# captouch_reva.net
KiCad netlist of a schematic drawn in EAGLE
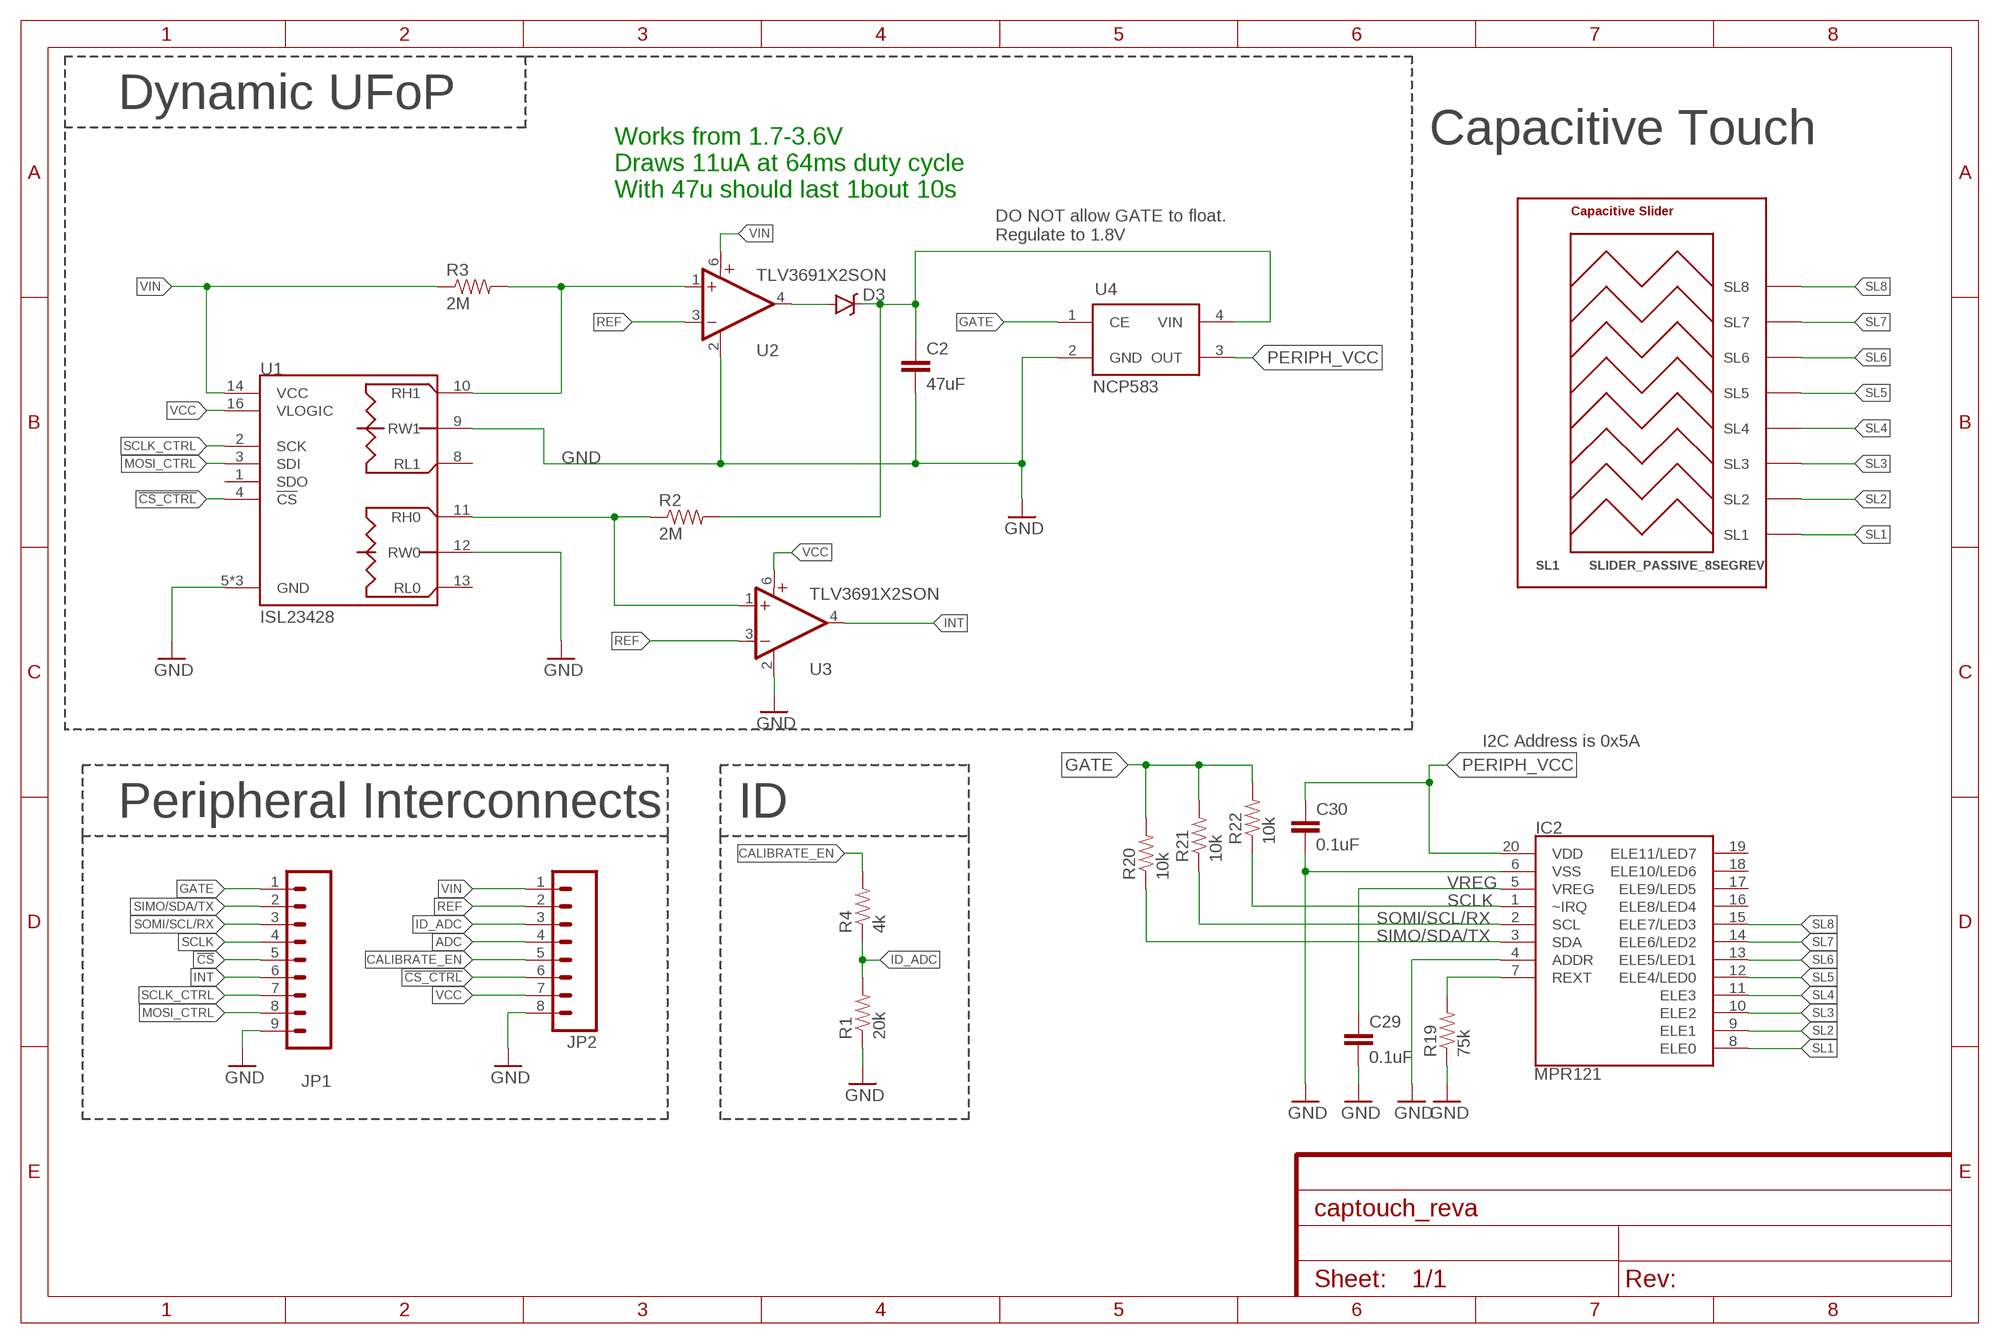
[diagram p0: schematic, sheet 1]

(export (version "E")
  (design (tool "Eeschema 10.0.6"))
  (components
    (comp (ref "C2")
      (value "47uF")
      (footprint "eagle-import:0805")
      (fields (field (name "MPN") "GRM21BR60J476ME15L"))
      (libsource (lib "eagle-import") (part "CAP0805"))
    )
    (comp (ref "C29")
      (value "0.1uF")
      (footprint "eagle-import:0402")
      (fields (field (name "MPN") "0402YD104KAT2A"))
      (libsource (lib "eagle-import") (part "C-EU"))
    )
    (comp (ref "C30")
      (value "0.1uF")
      (footprint "eagle-import:0402")
      (fields (field (name "MPN") "0402YD104KAT2A"))
      (libsource (lib "eagle-import") (part "C-EU"))
    )
    (comp (ref "D3")
      (value "RB751")
      (footprint "eagle-import:SOD-523")
      (fields (field (name "MPN") "BAS40-02V-V-G-08"))
      (libsource (lib "eagle-import") (part "DIODE-SCHOTTKY-RB751"))
    )
    (comp (ref "IC2")
      (value "MPR121")
      (footprint "eagle-import:QFN-20-0.4MM-V2")
      (fields (field (name "MPN") "MPR121QR2 "))
      (libsource (lib "eagle-import") (part "MPR121V2"))
    )
    (comp (ref "JP1")
      (value "M091.27MM")
      (footprint "eagle-import:1X09-1.27MM")
      (fields (field (name "MPN") "GRPB091VWVN-RC "))
      (libsource (lib "eagle-import") (part "M091.27MM"))
    )
    (comp (ref "JP2")
      (value "M081.27MM")
      (footprint "eagle-import:1X08-1.27MM")
      (fields (field (name "MPN") "GRPB081VWVN-RC "))
      (libsource (lib "eagle-import") (part "M081.27MM"))
    )
    (comp (ref "R1")
      (value "20k")
      (footprint "eagle-import:0402")
      (fields (field (name "MPN") "ERJ-2RKF2002X"))
      (libsource (lib "eagle-import") (part "R-EU"))
    )
    (comp (ref "R2")
      (value "2M")
      (footprint "eagle-import:0402")
      (fields (field (name "MPN") "RC1005F205CS"))
      (libsource (lib "eagle-import") (part "R-EU"))
    )
    (comp (ref "R3")
      (value "2M")
      (footprint "eagle-import:0402")
      (fields (field (name "MPN") "RC1005F205CS"))
      (libsource (lib "eagle-import") (part "R-EU"))
    )
    (comp (ref "R4")
      (value "4k")
      (footprint "eagle-import:0402")
      (fields (field (name "MPN") "RC0402FR-074K02L"))
      (libsource (lib "eagle-import") (part "R-EU"))
    )
    (comp (ref "R19")
      (value "75k")
      (footprint "eagle-import:0402")
      (fields (field (name "MPN") "RC0402FR-0775KL"))
      (libsource (lib "eagle-import") (part "R-EU"))
    )
    (comp (ref "R20")
      (value "10k")
      (footprint "eagle-import:0402")
      (fields (field (name "MPN") "ERJ-2RKF1002X"))
      (libsource (lib "eagle-import") (part "R-EU"))
    )
    (comp (ref "R21")
      (value "10k")
      (footprint "eagle-import:0402")
      (fields (field (name "MPN") "ERJ-2RKF1002X"))
      (libsource (lib "eagle-import") (part "R-EU"))
    )
    (comp (ref "R22")
      (value "10k")
      (footprint "eagle-import:0402")
      (fields (field (name "MPN") "ERJ-2RKF1002X"))
      (libsource (lib "eagle-import") (part "R-EU"))
    )
    (comp (ref "SL1")
      (value "SLIDER_PASSIVE_8SEGREV")
      (footprint "eagle-import:SLIDER_PASSIVE_8SEG_12MM_REV")
      (libsource (lib "eagle-import") (part "SLIDER_PASSIVE_8SEGREV"))
    )
    (comp (ref "U1")
      (value "ISL23428")
      (footprint "eagle-import:UTQFN-16")
      (fields (field (name "MPN") "ISL23428TFRUZ-T7A"))
      (libsource (lib "eagle-import") (part "ISL23428"))
    )
    (comp (ref "U2")
      (value "TLV3691X2SON")
      (footprint "eagle-import:X2SON")
      (fields (field (name "MPN") "TLV3691IDPFR"))
      (libsource (lib "eagle-import") (part "TLV3691X2SON"))
    )
    (comp (ref "U3")
      (value "TLV3691X2SON")
      (footprint "eagle-import:X2SON")
      (fields (field (name "MPN") "TLV3691IDPFR"))
      (libsource (lib "eagle-import") (part "TLV3691X2SON"))
    )
    (comp (ref "U4")
      (value "NCP583")
      (footprint "eagle-import:SC82-AB_1PRIMARY")
      (fields (field (name "MPN") "NCP583SQ18T1G"))
      (libsource (lib "eagle-import") (part "NCP583"))
    )
  )
  (nets
    (net (code "1") (name "/VREG") (class "Default")
      (node (ref "C29") (pin "1") (pinfunction "1_1") (pintype "passive"))
      (node (ref "IC2") (pin "5") (pinfunction "VREG_5") (pintype "bidirectional"))
    )
    (net (code "2") (name "/~{CS_CTRL}") (class "Default")
      (node (ref "JP2") (pin "6") (pinfunction "6_6") (pintype "passive"))
      (node (ref "U1") (pin "4") (pinfunction "~{CS}_4") (pintype "bidirectional"))
    )
    (net (code "3") (name "/~{CS}") (class "Default")
      (node (ref "JP1") (pin "5") (pinfunction "5_5") (pintype "passive"))
    )
    (net (code "4") (name "ADC") (class "Default")
      (node (ref "JP2") (pin "4") (pinfunction "4_4") (pintype "passive"))
    )
    (net (code "5") (name "CALIBRATE_EN") (class "Default")
      (node (ref "JP2") (pin "5") (pinfunction "5_5") (pintype "passive"))
      (node (ref "R4") (pin "2") (pinfunction "2_2") (pintype "passive"))
    )
    (net (code "6") (name "GATE") (class "Default")
      (node (ref "JP1") (pin "1") (pinfunction "1_1") (pintype "passive"))
      (node (ref "R20") (pin "2") (pinfunction "2_2") (pintype "passive"))
      (node (ref "R21") (pin "2") (pinfunction "2_2") (pintype "passive"))
      (node (ref "R22") (pin "2") (pinfunction "2_2") (pintype "passive"))
      (node (ref "U4") (pin "1") (pinfunction "CE_1") (pintype "bidirectional"))
    )
    (net (code "7") (name "GND") (class "Default")
      (node (ref "C2") (pin "2") (pinfunction "2_2") (pintype "passive"))
      (node (ref "C29") (pin "2") (pinfunction "2_2") (pintype "passive"))
      (node (ref "C30") (pin "2") (pinfunction "2_2") (pintype "passive"))
      (node (ref "IC2") (pin "4") (pinfunction "ADDR_4") (pintype "bidirectional"))
      (node (ref "IC2") (pin "6") (pinfunction "VSS_6") (pintype "bidirectional"))
      (node (ref "JP1") (pin "9") (pinfunction "9_9") (pintype "passive"))
      (node (ref "JP2") (pin "8") (pinfunction "8_8") (pintype "passive"))
      (node (ref "R1") (pin "1") (pinfunction "1_1") (pintype "passive"))
      (node (ref "R19") (pin "1") (pinfunction "1_1") (pintype "passive"))
      (node (ref "U1") (pin "12") (pinfunction "RW0_12") (pintype "bidirectional"))
      (node (ref "U1") (pin "15") (pinfunction "GND_15") (pintype "bidirectional"))
      (node (ref "U1") (pin "5") (pinfunction "GND_5") (pintype "bidirectional"))
      (node (ref "U1") (pin "6") (pinfunction "GND_6") (pintype "bidirectional"))
      (node (ref "U1") (pin "9") (pinfunction "RW1_9") (pintype "bidirectional"))
      (node (ref "U2") (pin "2") (pinfunction "GND_2") (pintype "power_in"))
      (node (ref "U3") (pin "2") (pinfunction "GND_2") (pintype "power_in"))
      (node (ref "U4") (pin "2") (pinfunction "GND_2") (pintype "bidirectional"))
    )
    (net (code "8") (name "ID_ADC") (class "Default")
      (node (ref "JP2") (pin "3") (pinfunction "3_3") (pintype "passive"))
      (node (ref "R1") (pin "2") (pinfunction "2_2") (pintype "passive"))
      (node (ref "R4") (pin "1") (pinfunction "1_1") (pintype "passive"))
    )
    (net (code "9") (name "INT") (class "Default")
      (node (ref "JP1") (pin "6") (pinfunction "6_6") (pintype "passive"))
      (node (ref "U3") (pin "4") (pinfunction "OUT_4") (pintype "output"))
    )
    (net (code "10") (name "MOSI_CTRL") (class "Default")
      (node (ref "JP1") (pin "8") (pinfunction "8_8") (pintype "passive"))
      (node (ref "U1") (pin "3") (pinfunction "SDI_3") (pintype "bidirectional"))
    )
    (net (code "11") (name "Net-(IC2-REXT)") (class "Default")
      (node (ref "IC2") (pin "7") (pinfunction "REXT_7") (pintype "bidirectional"))
      (node (ref "R19") (pin "2") (pinfunction "2_2") (pintype "passive"))
    )
    (net (code "12") (name "Net-(U1-RH0)") (class "Default")
      (node (ref "R2") (pin "1") (pinfunction "1_1") (pintype "passive"))
      (node (ref "U1") (pin "11") (pinfunction "RH0_11") (pintype "bidirectional"))
      (node (ref "U3") (pin "1") (pinfunction "+IN_1") (pintype "input"))
    )
    (net (code "13") (name "Net-(U1-RH1)") (class "Default")
      (node (ref "R3") (pin "2") (pinfunction "2_2") (pintype "passive"))
      (node (ref "U1") (pin "10") (pinfunction "RH1_10") (pintype "bidirectional"))
      (node (ref "U2") (pin "1") (pinfunction "+IN_1") (pintype "input"))
    )
    (net (code "14") (name "Net-(U2-OUT)") (class "Default")
      (node (ref "D3") (pin "A") (pinfunction "A_A") (pintype "passive"))
      (node (ref "U2") (pin "4") (pinfunction "OUT_4") (pintype "output"))
    )
    (net (code "15") (name "Net-(U4-VIN)") (class "Default")
      (node (ref "C2") (pin "1") (pinfunction "1_1") (pintype "passive"))
      (node (ref "D3") (pin "C") (pinfunction "C_C") (pintype "passive"))
      (node (ref "R2") (pin "2") (pinfunction "2_2") (pintype "passive"))
      (node (ref "U4") (pin "4") (pinfunction "VIN_4") (pintype "bidirectional"))
    )
    (net (code "16") (name "PERIPH_VCC") (class "Default")
      (node (ref "C30") (pin "1") (pinfunction "1_1") (pintype "passive"))
      (node (ref "IC2") (pin "20") (pinfunction "VDD_20") (pintype "bidirectional"))
      (node (ref "U4") (pin "3") (pinfunction "OUT_3") (pintype "bidirectional"))
    )
    (net (code "17") (name "REF") (class "Default")
      (node (ref "JP2") (pin "2") (pinfunction "2_2") (pintype "passive"))
      (node (ref "U2") (pin "3") (pinfunction "-IN_3") (pintype "input"))
      (node (ref "U3") (pin "3") (pinfunction "-IN_3") (pintype "input"))
    )
    (net (code "18") (name "SCLK") (class "Default")
      (node (ref "IC2") (pin "1") (pinfunction "~{IRQ}_1") (pintype "bidirectional"))
      (node (ref "JP1") (pin "4") (pinfunction "4_4") (pintype "passive"))
      (node (ref "R22") (pin "1") (pinfunction "1_1") (pintype "passive"))
    )
    (net (code "19") (name "SCLK_CTRL") (class "Default")
      (node (ref "JP1") (pin "7") (pinfunction "7_7") (pintype "passive"))
      (node (ref "U1") (pin "2") (pinfunction "SCK_2") (pintype "bidirectional"))
    )
    (net (code "20") (name "SIMO{slash}SDA{slash}TX") (class "Default")
      (node (ref "IC2") (pin "3") (pinfunction "SDA_3") (pintype "bidirectional"))
      (node (ref "JP1") (pin "2") (pinfunction "2_2") (pintype "passive"))
      (node (ref "R20") (pin "1") (pinfunction "1_1") (pintype "passive"))
    )
    (net (code "21") (name "SL1") (class "Default")
      (node (ref "IC2") (pin "8") (pinfunction "ELE0_8") (pintype "bidirectional"))
      (node (ref "SL1") (pin "SL1") (pinfunction "SL1_SL1") (pintype "passive"))
    )
    (net (code "22") (name "SL2") (class "Default")
      (node (ref "IC2") (pin "9") (pinfunction "ELE1_9") (pintype "bidirectional"))
      (node (ref "SL1") (pin "SL2") (pinfunction "SL2_SL2") (pintype "passive"))
    )
    (net (code "23") (name "SL3") (class "Default")
      (node (ref "IC2") (pin "10") (pinfunction "ELE2_10") (pintype "bidirectional"))
      (node (ref "SL1") (pin "SL3") (pinfunction "SL3_SL3") (pintype "passive"))
    )
    (net (code "24") (name "SL4") (class "Default")
      (node (ref "IC2") (pin "11") (pinfunction "ELE3_11") (pintype "bidirectional"))
      (node (ref "SL1") (pin "SL4") (pinfunction "SL4_SL4") (pintype "passive"))
    )
    (net (code "25") (name "SL5") (class "Default")
      (node (ref "IC2") (pin "12") (pinfunction "ELE4/LED0_12") (pintype "bidirectional"))
      (node (ref "SL1") (pin "SL5") (pinfunction "SL5_SL5") (pintype "passive"))
    )
    (net (code "26") (name "SL6") (class "Default")
      (node (ref "IC2") (pin "13") (pinfunction "ELE5/LED1_13") (pintype "bidirectional"))
      (node (ref "SL1") (pin "SL6") (pinfunction "SL6_SL6") (pintype "passive"))
    )
    (net (code "27") (name "SL7") (class "Default")
      (node (ref "IC2") (pin "14") (pinfunction "ELE6/LED2_14") (pintype "bidirectional"))
      (node (ref "SL1") (pin "SL7") (pinfunction "SL7_SL7") (pintype "passive"))
    )
    (net (code "28") (name "SL8") (class "Default")
      (node (ref "IC2") (pin "15") (pinfunction "ELE7/LED3_15") (pintype "bidirectional"))
      (node (ref "SL1") (pin "SL8") (pinfunction "SL8_SL8") (pintype "passive"))
    )
    (net (code "29") (name "SOMI{slash}SCL{slash}RX") (class "Default")
      (node (ref "IC2") (pin "2") (pinfunction "SCL_2") (pintype "bidirectional"))
      (node (ref "JP1") (pin "3") (pinfunction "3_3") (pintype "passive"))
      (node (ref "R21") (pin "1") (pinfunction "1_1") (pintype "passive"))
    )
    (net (code "30") (name "VCC") (class "Default")
      (node (ref "JP2") (pin "7") (pinfunction "7_7") (pintype "passive"))
      (node (ref "U1") (pin "16") (pinfunction "VLOGIC_16") (pintype "bidirectional"))
      (node (ref "U3") (pin "6") (pinfunction "V+_6") (pintype "power_in"))
    )
    (net (code "31") (name "VIN") (class "Default")
      (node (ref "JP2") (pin "1") (pinfunction "1_1") (pintype "passive"))
      (node (ref "R3") (pin "1") (pinfunction "1_1") (pintype "passive"))
      (node (ref "U1") (pin "14") (pinfunction "VCC_14") (pintype "bidirectional"))
      (node (ref "U2") (pin "6") (pinfunction "V+_6") (pintype "power_in"))
    )
    (net (code "32") (name "unconnected-(IC2-ELE8{slash}LED4-Pad16)") (class "Default")
      (node (ref "IC2") (pin "16") (pinfunction "ELE8/LED4_16") (pintype "bidirectional"))
    )
    (net (code "33") (name "unconnected-(IC2-ELE9{slash}LED5-Pad17)") (class "Default")
      (node (ref "IC2") (pin "17") (pinfunction "ELE9/LED5_17") (pintype "bidirectional"))
    )
    (net (code "34") (name "unconnected-(IC2-ELE10{slash}LED6-Pad18)") (class "Default")
      (node (ref "IC2") (pin "18") (pinfunction "ELE10/LED6_18") (pintype "bidirectional"))
    )
    (net (code "35") (name "unconnected-(IC2-ELE11{slash}LED7-Pad19)") (class "Default")
      (node (ref "IC2") (pin "19") (pinfunction "ELE11/LED7_19") (pintype "bidirectional"))
    )
    (net (code "36") (name "unconnected-(U1-RL0-Pad13)") (class "Default")
      (node (ref "U1") (pin "13") (pinfunction "RL0_13") (pintype "bidirectional"))
    )
    (net (code "37") (name "unconnected-(U1-RL1-Pad8)") (class "Default")
      (node (ref "U1") (pin "8") (pinfunction "RL1_8") (pintype "bidirectional"))
    )
    (net (code "38") (name "unconnected-(U1-SDO-Pad1)") (class "Default")
      (node (ref "U1") (pin "1") (pinfunction "SDO_1") (pintype "bidirectional"))
    )
  )
)
